# design.net
KiCad netlist of a schematic drawn in Altium Designer
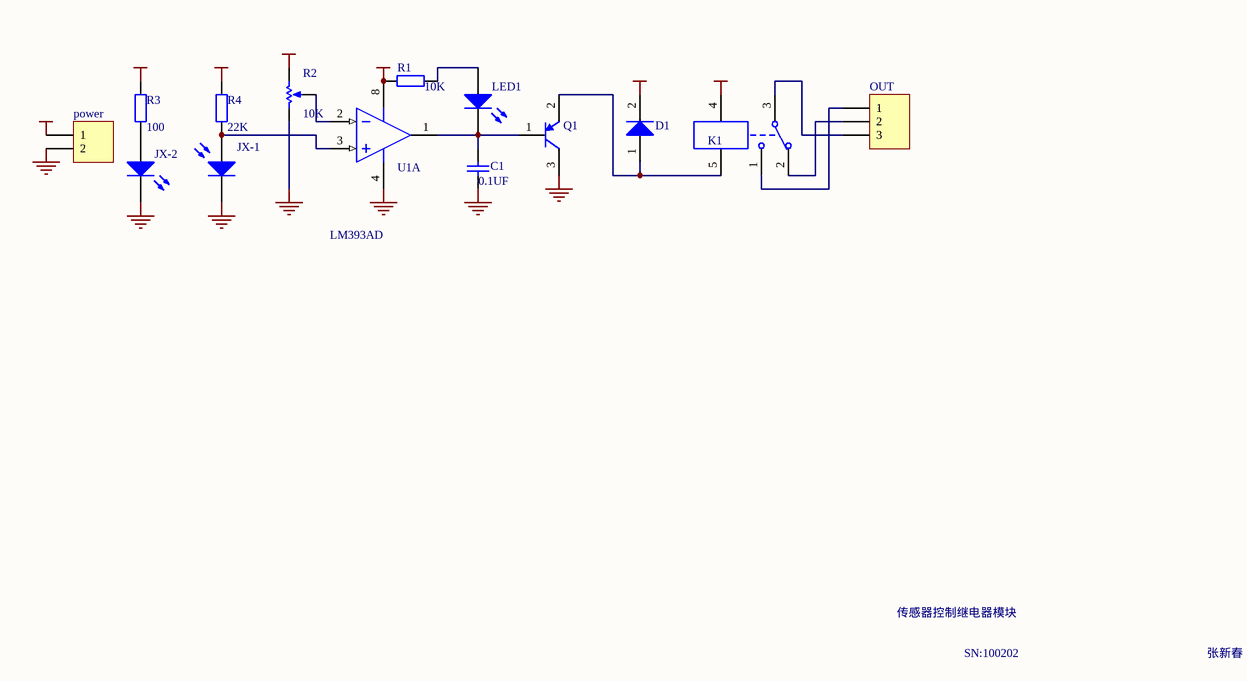
[diagram p0: 传感器控制继电器模块.SCHDOC]

(export (version "E")
  (design (tool "Eeschema 10.0.6"))
  (components
    (comp (ref "C1")
      (value "0.1UF")
      (footprint "HDR1X2")
      (description "Capacitor (Semiconductor SIM Model)")
      (fields (field (name "PUBLISHER") "Altium Limited"))
      (libsource (lib "Miscellaneous Devices") (part "Cap Semi"))
    )
    (comp (ref "D1")
      (value "ZL2JG")
      (footprint "D-ZL-10")
      (description "整流二极管")
      (fields (field (name "PUBLISHER") "Altium Limited"))
      (libsource (lib "zxcourhc") (part "ZL2JG"))
    )
    (comp (ref "JX-1")
      (value "~")
      (footprint "HDR1X2")
      (description "Photosensitive Diode")
      (fields (field (name "PUBLISHER") "Altium Limited"))
      (libsource (lib "Miscellaneous Devices") (part "Photo Sen"))
    )
    (comp (ref "JX-2")
      (value "~")
      (footprint "HDR1X2")
      (description "Typical BLUE SiC LED")
      (fields (field (name "PUBLISHER") "Altium Limited"))
      (libsource (lib "Miscellaneous Devices") (part "LED3"))
    )
    (comp (ref "K1")
      (value "JDQYCK")
      (footprint "JQC-3F/T73")
      (description "继电器——1常开1常闭")
      (fields (field (name "PUBLISHER") "Altium Limited"))
      (libsource (lib "zxcourhc") (part "JDQYCK"))
    )
    (comp (ref "LED1")
      (value "~")
      (footprint "HDR1X2")
      (description "Typical BLUE SiC LED")
      (fields (field (name "PUBLISHER") "Altium Limited"))
      (libsource (lib "Miscellaneous Devices") (part "LED3"))
    )
    (comp (ref "OUT")
      (value "PZ_3")
      (footprint "JK128_3")
      (description "排针——3")
      (fields (field (name "PUBLISHER") "Altium Limited"))
      (libsource (lib "zxcourhc") (part "PZ_3"))
    )
    (comp (ref "power")
      (value "PZ_2")
      (footprint "DYDZ")
      (description "排针——2")
      (fields (field (name "PUBLISHER") "Altium Limited"))
      (libsource (lib "zxcourhc") (part "PZ_2"))
    )
    (comp (ref "Q1")
      (value "TPSJG_PNP")
      (footprint "SO-G3")
      (description "贴片三极管——PNP")
      (fields (field (name "PUBLISHER") "Altium Limited"))
      (libsource (lib "zxcourhc") (part "TPSJG_PNP"))
    )
    (comp (ref "R1")
      (value "10K")
      (footprint "HDR1X2")
      (description "Resistor")
      (fields (field (name "PUBLISHER") "Altium Limited"))
      (libsource (lib "") (part "Res2_1"))
    )
    (comp (ref "R2")
      (value "10K")
      (footprint "SIP3-D")
      (description "Potentiometer")
      (fields (field (name "PUBLISHER") "Altium Limited"))
      (libsource (lib "Miscellaneous Devices") (part "RPot"))
    )
    (comp (ref "R3")
      (value "100")
      (footprint "HDR1X2")
      (description "Resistor")
      (fields (field (name "PUBLISHER") "Altium Limited"))
      (libsource (lib "Miscellaneous Devices") (part "Res2"))
    )
    (comp (ref "R4")
      (value "22K")
      (footprint "HDR1X2")
      (description "Resistor")
      (fields (field (name "PUBLISHER") "Altium Limited"))
      (libsource (lib "Miscellaneous Devices") (part "Res2"))
    )
    (comp (ref "U1")
      (value "LM393AD")
      (footprint "CDFP-8")
      (description "Low-Power Dual Voltage Comparator")
      (fields (field (name "PUBLISHER") "Altium Limited"))
      (libsource (lib "ST Analog Comparator") (part "LM393AD"))
    )
  )
  (nets
    (net (code "1") (name "GND") (class "Default")
      (node (ref "C1") (pin "1") (pinfunction "1_1") (pintype "passive"))
      (node (ref "JX-1") (pin "2") (pinfunction "K_2") (pintype "passive"))
      (node (ref "JX-2") (pin "2") (pinfunction "K_2") (pintype "passive"))
      (node (ref "Q1") (pin "3") (pinfunction "C_3") (pintype "passive"))
      (node (ref "R2") (pin "2") (pinfunction "BOT_2") (pintype "passive"))
      (node (ref "U1") (pin "4") (pinfunction "V-_4") (pintype "power_in"))
      (node (ref "power") (pin "2") (pinfunction "2_2") (pintype "passive"))
    )
    (net (code "2") (name "Net-(D1-A)") (class "Default")
      (node (ref "D1") (pin "1") (pinfunction "A_1") (pintype "passive"))
      (node (ref "K1") (pin "5") (pinfunction "5_5") (pintype "passive"))
      (node (ref "Q1") (pin "2") (pinfunction "E_2") (pintype "passive"))
    )
    (net (code "3") (name "Net-(JX-1-A)") (class "Default")
      (node (ref "JX-1") (pin "1") (pinfunction "A_1") (pintype "passive"))
      (node (ref "R4") (pin "1") (pinfunction "1_1") (pintype "passive"))
      (node (ref "U1") (pin "3") (pinfunction "IN+_3") (pintype "input"))
    )
    (net (code "4") (name "Net-(JX-2-A)") (class "Default")
      (node (ref "JX-2") (pin "1") (pinfunction "A_1") (pintype "passive"))
      (node (ref "R3") (pin "1") (pinfunction "1_1") (pintype "passive"))
    )
    (net (code "5") (name "Net-(K1-Pad1)") (class "Default")
      (node (ref "K1") (pin "1") (pinfunction "1_1") (pintype "passive"))
      (node (ref "OUT") (pin "1") (pinfunction "1_1") (pintype "passive"))
    )
    (net (code "6") (name "Net-(K1-Pad2)") (class "Default")
      (node (ref "K1") (pin "2") (pinfunction "2_2") (pintype "passive"))
      (node (ref "OUT") (pin "2") (pinfunction "2_2") (pintype "passive"))
    )
    (net (code "7") (name "Net-(K1-Pad3)") (class "Default")
      (node (ref "K1") (pin "3") (pinfunction "3_3") (pintype "passive"))
      (node (ref "OUT") (pin "3") (pinfunction "3_3") (pintype "passive"))
    )
    (net (code "8") (name "Net-(LED1-A)") (class "Default")
      (node (ref "LED1") (pin "1") (pinfunction "A_1") (pintype "passive"))
      (node (ref "R1") (pin "1") (pinfunction "1_1") (pintype "passive"))
    )
    (net (code "9") (name "Net-(LED1-K)") (class "Default")
      (node (ref "C1") (pin "2") (pinfunction "2_2") (pintype "passive"))
      (node (ref "LED1") (pin "2") (pinfunction "K_2") (pintype "passive"))
      (node (ref "Q1") (pin "1") (pinfunction "B_1") (pintype "passive"))
      (node (ref "U1") (pin "1") (pinfunction "OUT_1") (pintype "open_collector"))
    )
    (net (code "10") (name "Net-(R2-TAP)") (class "Default")
      (node (ref "R2") (pin "3") (pinfunction "TAP_3") (pintype "passive"))
      (node (ref "U1") (pin "2") (pinfunction "IN-_2") (pintype "input"))
    )
    (net (code "11") (name "VCC") (class "Default")
      (node (ref "D1") (pin "2") (pinfunction "K_2") (pintype "passive"))
      (node (ref "K1") (pin "4") (pinfunction "4_4") (pintype "passive"))
      (node (ref "R1") (pin "2") (pinfunction "2_2") (pintype "passive"))
      (node (ref "R2") (pin "1") (pinfunction "TOP_1") (pintype "passive"))
      (node (ref "R3") (pin "2") (pinfunction "2_2") (pintype "passive"))
      (node (ref "R4") (pin "2") (pinfunction "2_2") (pintype "passive"))
      (node (ref "U1") (pin "8") (pinfunction "V+_8") (pintype "power_in"))
      (node (ref "power") (pin "1") (pinfunction "1_1") (pintype "passive"))
    )
  )
)
